# TempSensor.net
KiCad netlist of a schematic drawn in Altium Designer
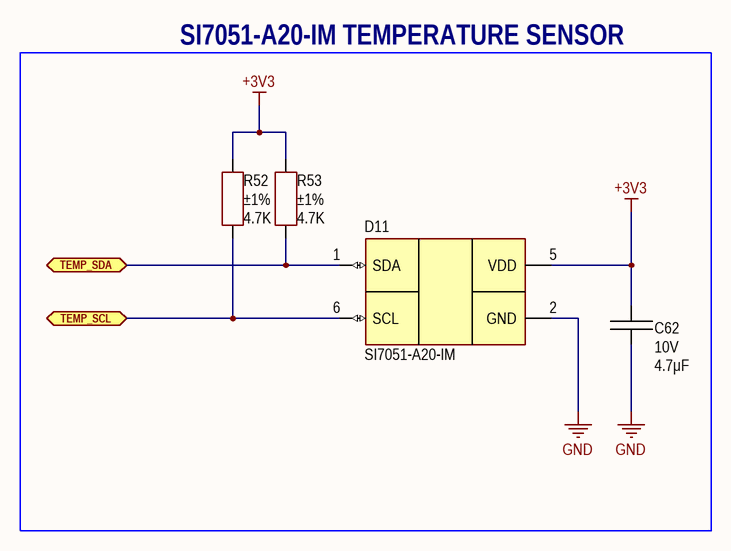
[diagram p0: TempSensor.SchDoc]

(export (version "E")
  (design (tool "Eeschema 10.0.6"))
  (components
    (comp (ref "C62")
      (value "4.7μF")
      (footprint "CAP: 0805")
      (description "4.7 µF ±10% 16V Ceramic Capacitor X7R 0805 (2012 Metric)")
      (fields
        (field (name "MANUFACTURER") "Yageo")
        (field (name "PARTNUMBER") "CC0805KKX7R7BB475")
        (field (name "VOLTAGE") "10V")
      )
      (libsource (lib "capacitor") (part "Ceramic_0805"))
    )
    (comp (ref "D11")
      (value "~")
      (footprint "6-WDFN(3x3)")
      (description "Temperature sensor")
      (fields
        (field (name "MANUFACTURER") "Silicon Labs")
        (field (name "VALUEMANUFACTURERPARTNUMBER") "IC temperature sensor, Digital sensor, ±0.1°C, , , -40...+125°C, 6-WDFN")
        (field (name "PARTNUMBER") "SI7051-A20-IM")
      )
      (libsource (lib "MyLib") (part "SI7051-A20-IM"))
    )
    (comp (ref "R52")
      (value "4.7K")
      (footprint "RES: 0805")
      (description "4.7 kOhms ±5% 0.125W, 1/8W Chip Resistor 0805 (2012 Metric) Moisture Resistant Thick Film")
      (fields
        (field (name "MANUFACTURER") "Yageo")
        (field (name "PARTNUMBER") "RC0805JR-074K7L")
        (field (name "TOLERANCE") "±1%")
      )
      (libsource (lib "resistor") (part "Resistor_0805"))
    )
    (comp (ref "R53")
      (value "4.7K")
      (footprint "RES: 0805")
      (description "4.7 kOhms ±5% 0.125W, 1/8W Chip Resistor 0805 (2012 Metric) Moisture Resistant Thick Film")
      (fields
        (field (name "MANUFACTURER") "Yageo")
        (field (name "PARTNUMBER") "RC0805JR-074K7L")
        (field (name "TOLERANCE") "±1%")
      )
      (libsource (lib "resistor") (part "Resistor_0805"))
    )
  )
  (nets
    (net (code "1") (name "+3V3") (class "Default")
      (node (ref "C62") (pin "2") (pinfunction "2_2") (pintype "passive"))
      (node (ref "D11") (pin "5") (pinfunction "VDD_5") (pintype "power_in"))
      (node (ref "R52") (pin "1") (pinfunction "1_1") (pintype "passive"))
      (node (ref "R53") (pin "1") (pinfunction "1_1") (pintype "passive"))
    )
    (net (code "2") (name "/TEMP_SCL") (class "Default")
      (node (ref "D11") (pin "6") (pinfunction "SCL_6") (pintype "bidirectional"))
      (node (ref "R52") (pin "2") (pinfunction "2_2") (pintype "passive"))
    )
    (net (code "3") (name "/TEMP_SDA") (class "Default")
      (node (ref "D11") (pin "1") (pinfunction "SDA_1") (pintype "bidirectional"))
      (node (ref "R53") (pin "2") (pinfunction "2_2") (pintype "passive"))
    )
    (net (code "4") (name "GND") (class "Default")
      (node (ref "C62") (pin "1") (pinfunction "1_1") (pintype "passive"))
      (node (ref "D11") (pin "2") (pinfunction "GND_2") (pintype "power_in"))
    )
  )
)
